# SparkFun_Lipo_Charger_Basic-microUSB.net
KiCad netlist of a schematic drawn in EAGLE
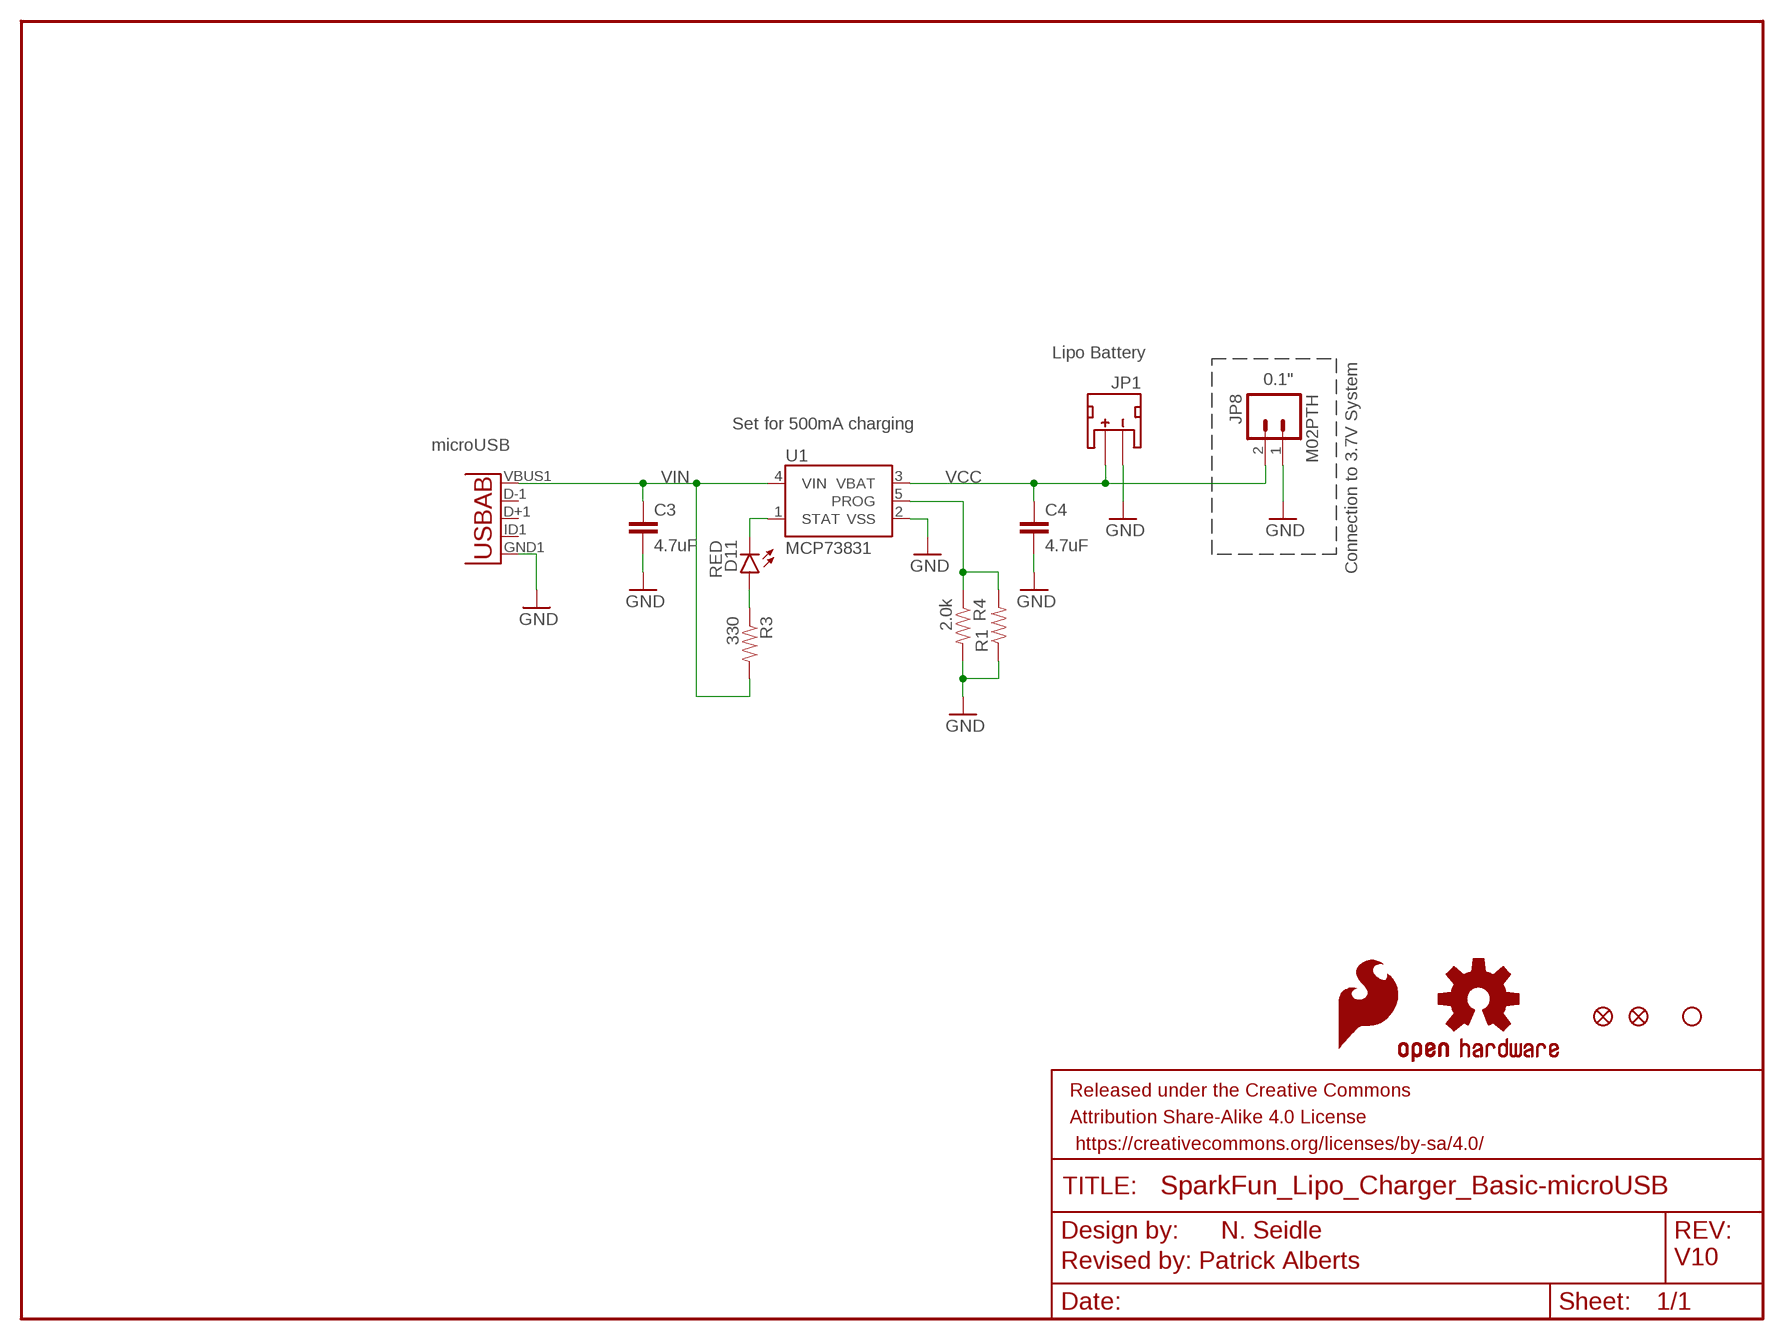
[diagram p0: schematic, sheet 1]

(export (version "E")
  (design (tool "Eeschema 10.0.6"))
  (components
    (comp (ref "C3")
      (value "4.7uF")
      (footprint "eagle-import:0603-CAP")
      (libsource (lib "eagle-import") (part "4.7UF-6.3V-10%(0603)0603"))
    )
    (comp (ref "C4")
      (value "4.7uF")
      (footprint "eagle-import:0603-CAP")
      (libsource (lib "eagle-import") (part "4.7UF-6.3V-10%(0603)0603"))
    )
    (comp (ref "D11")
      (value "RED")
      (footprint "eagle-import:LED-0603")
      (libsource (lib "eagle-import") (part "LED-RED0603"))
    )
    (comp (ref "FRAME1")
      (value "FRAME-LETTER")
      (footprint "eagle-import:CREATIVE_COMMONS")
      (libsource (lib "eagle-import") (part "FRAME-LETTER"))
    )
    (comp (ref "JP1")
      (value "JST")
      (footprint "eagle-import:JST-2-SMD")
      (libsource (lib "eagle-import") (part "JST_2MM_MALE"))
    )
    (comp (ref "JP2")
      (value "STAND-OFF")
      (footprint "eagle-import:STAND-OFF")
      (libsource (lib "eagle-import") (part "STAND-OFF"))
    )
    (comp (ref "JP3")
      (value "FIDUCIAL1X2")
      (footprint "eagle-import:FIDUCIAL-1X2")
      (libsource (lib "eagle-import") (part "FIDUCIAL1X2"))
    )
    (comp (ref "JP4")
      (value "FIDUCIAL1X2")
      (footprint "eagle-import:FIDUCIAL-1X2")
      (libsource (lib "eagle-import") (part "FIDUCIAL1X2"))
    )
    (comp (ref "JP8")
      (value "M02PTH")
      (footprint "eagle-import:1X02")
      (libsource (lib "eagle-import") (part "M02PTH"))
    )
    (comp (ref "JP9")
      (value "Micro USB")
      (footprint "eagle-import:USB-AB-MICRO-SMD_V03")
      (libsource (lib "eagle-import") (part "USB-ABCONN-11794"))
    )
    (comp (ref "LOGO1")
      (value "OSHW-LOGOS")
      (footprint "eagle-import:OSHW-LOGO-S")
      (libsource (lib "eagle-import") (part "OSHW-LOGOS"))
    )
    (comp (ref "LOGO2")
      (value "SFE_LOGO_FLAME.1_INCH")
      (footprint "eagle-import:SFE_LOGO_FLAME_.1")
      (libsource (lib "eagle-import") (part "SFE_LOGO_FLAME.1_INCH"))
    )
    (comp (ref "R1")
      (value "RESISTORPTH-1/4W-VERT-KIT")
      (footprint "eagle-import:AXIAL-0.1EZ")
      (libsource (lib "eagle-import") (part "RESISTORPTH-1/4W-VERT-KIT"))
    )
    (comp (ref "R3")
      (value "330")
      (footprint "eagle-import:0603-RES")
      (libsource (lib "eagle-import") (part "330OHM1/10W1%(0603)"))
    )
    (comp (ref "R4")
      (value "2.0k")
      (footprint "eagle-import:0603-RES")
      (libsource (lib "eagle-import") (part "2.0KOHM1/10W5%(0603)"))
    )
    (comp (ref "U1")
      (value "MCP73831")
      (footprint "eagle-import:SOT23-5")
      (libsource (lib "eagle-import") (part "MCP73831"))
    )
  )
  (nets
    (net (code "1") (name "/VCC") (class "Default")
      (node (ref "C4") (pin "1") (pinfunction "1_1") (pintype "passive"))
      (node (ref "JP1") (pin "2") (pinfunction "+_2") (pintype "bidirectional"))
      (node (ref "JP8") (pin "2") (pinfunction "2_2") (pintype "passive"))
      (node (ref "U1") (pin "3") (pinfunction "VBAT_3") (pintype "power_in"))
    )
    (net (code "2") (name "/VIN") (class "Default")
      (node (ref "C3") (pin "1") (pinfunction "1_1") (pintype "passive"))
      (node (ref "JP9") (pin "VBUS1") (pinfunction "VBUS_VBUS1") (pintype "bidirectional"))
      (node (ref "R3") (pin "2") (pinfunction "2_2") (pintype "passive"))
      (node (ref "U1") (pin "4") (pinfunction "VIN_4") (pintype "power_in"))
    )
    (net (code "3") (name "GND") (class "Default")
      (node (ref "C3") (pin "2") (pinfunction "2_2") (pintype "passive"))
      (node (ref "C4") (pin "2") (pinfunction "2_2") (pintype "passive"))
      (node (ref "JP1") (pin "1") (pinfunction "-_1") (pintype "bidirectional"))
      (node (ref "JP8") (pin "1") (pinfunction "1_1") (pintype "passive"))
      (node (ref "JP9") (pin "GND1") (pinfunction "GND_GND1") (pintype "bidirectional"))
      (node (ref "R1") (pin "P$1") (pinfunction "1_P$1") (pintype "passive"))
      (node (ref "R4") (pin "2") (pinfunction "2_2") (pintype "passive"))
      (node (ref "U1") (pin "2") (pinfunction "VSS_2") (pintype "power_in"))
    )
    (net (code "4") (name "Net-(D11-PadA)") (class "Default")
      (node (ref "D11") (pin "A") (pinfunction "A_A") (pintype "passive"))
      (node (ref "R3") (pin "1") (pinfunction "1_1") (pintype "passive"))
    )
    (net (code "5") (name "Net-(R1-2)") (class "Default")
      (node (ref "R1") (pin "P$2") (pinfunction "2_P$2") (pintype "passive"))
      (node (ref "R4") (pin "1") (pinfunction "1_1") (pintype "passive"))
      (node (ref "U1") (pin "5") (pinfunction "PROG_5") (pintype "input"))
    )
    (net (code "6") (name "Net-(U1-STAT)") (class "Default")
      (node (ref "D11") (pin "C") (pinfunction "C_C") (pintype "passive"))
      (node (ref "U1") (pin "1") (pinfunction "STAT_1") (pintype "output"))
    )
    (net (code "7") (name "unconnected-(JP1-PAD1-PadNC1)") (class "Default")
      (node (ref "JP1") (pin "NC1") (pinfunction "PAD1_NC1") (pintype "bidirectional"))
    )
    (net (code "8") (name "unconnected-(JP1-PAD2-PadNC2)") (class "Default")
      (node (ref "JP1") (pin "NC2") (pinfunction "PAD2_NC2") (pintype "bidirectional"))
    )
    (net (code "9") (name "unconnected-(JP9-D+-PadD+1)") (class "Default")
      (node (ref "JP9") (pin "D+1") (pinfunction "D+_D+1") (pintype "bidirectional"))
    )
    (net (code "10") (name "unconnected-(JP9-D--PadD-1)") (class "Default")
      (node (ref "JP9") (pin "D-1") (pinfunction "D-_D-1") (pintype "bidirectional"))
    )
    (net (code "11") (name "unconnected-(JP9-USBID-PadID1)") (class "Default")
      (node (ref "JP9") (pin "ID1") (pinfunction "USBID_ID1") (pintype "bidirectional"))
    )
  )
)
